# Core-Locobuffer.net
KiCad netlist of a schematic drawn in EAGLE
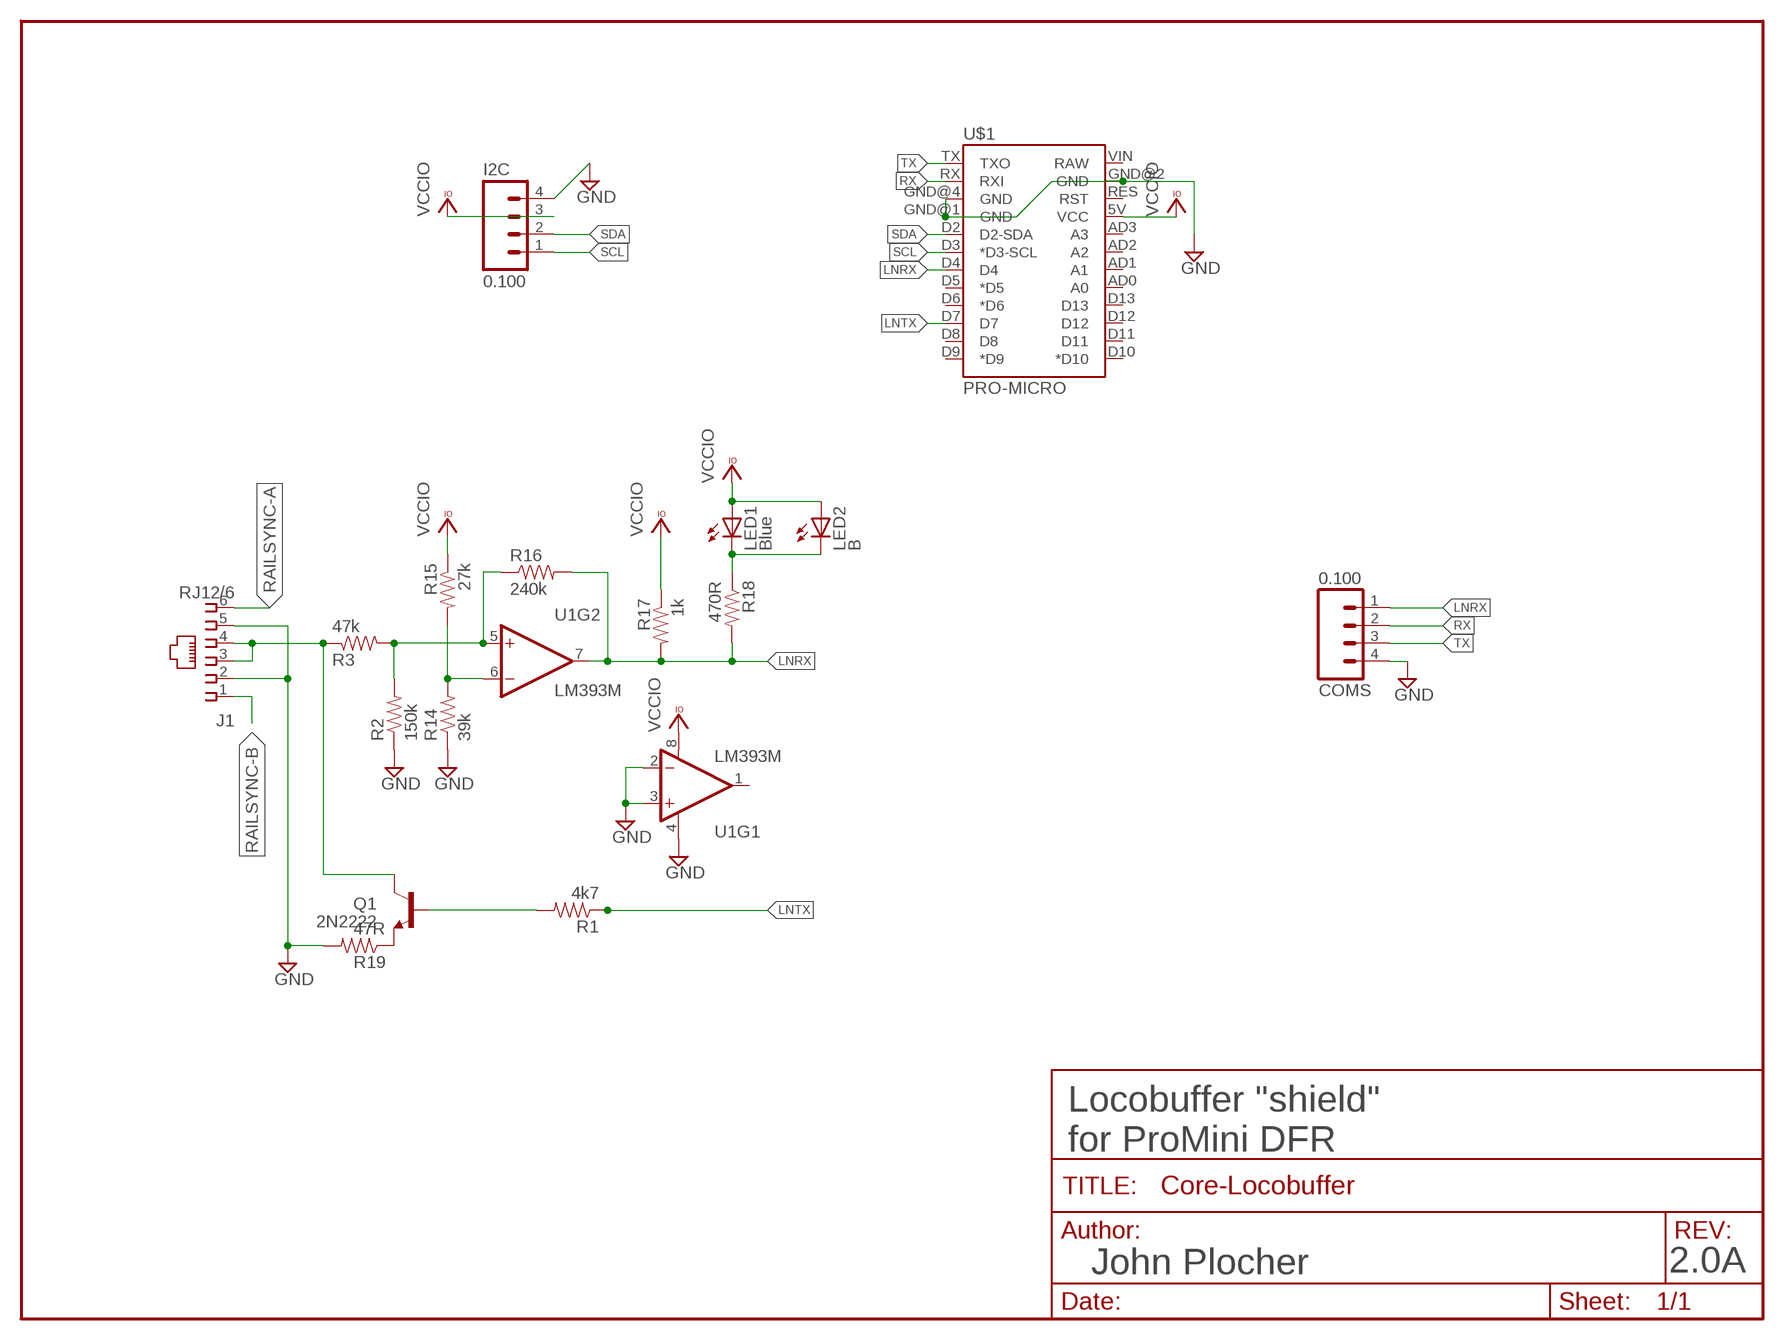
[diagram p0: schematic, sheet 1]

(export (version "E")
  (design (tool "Eeschema 10.0.6"))
  (components
    (comp (ref "COMS")
      (value "0.100")
      (footprint "eagle-import:1X04_LOCK")
      (libsource (lib "eagle-import") (part "CONNECTOR-M04LOCK"))
    )
    (comp (ref "I2C")
      (value "0.100")
      (footprint "eagle-import:1X04_LOCK")
      (libsource (lib "eagle-import") (part "CONNECTOR-M04LOCK"))
    )
    (comp (ref "J1")
      (value "RJ12/6")
      (footprint "eagle-import:RJ25-PANEL")
      (libsource (lib "eagle-import") (part "CONNECTOR-RJ25-6P6C"))
    )
    (comp (ref "LED1")
      (value "Blue")
      (footprint "eagle-import:0603-LED")
      (libsource (lib "eagle-import") (part "LED0603-LED"))
    )
    (comp (ref "LED2")
      (value "B")
      (footprint "eagle-import:LED5MM")
      (libsource (lib "eagle-import") (part "LEDLED5MM"))
    )
    (comp (ref "Q1")
      (value "2N2222")
      (footprint "eagle-import:SOT23")
      (libsource (lib "eagle-import") (part "NPN-SOT23"))
    )
    (comp (ref "R1")
      (value "4k7")
      (footprint "eagle-import:0603-RES")
      (libsource (lib "eagle-import") (part "R0603-RES"))
    )
    (comp (ref "R2")
      (value "150k")
      (footprint "eagle-import:0603-RES")
      (libsource (lib "eagle-import") (part "R0603-RES"))
    )
    (comp (ref "R3")
      (value "47k")
      (footprint "eagle-import:0603-RES")
      (libsource (lib "eagle-import") (part "R0603-RES"))
    )
    (comp (ref "R14")
      (value "39k")
      (footprint "eagle-import:0603-RES")
      (libsource (lib "eagle-import") (part "R0603-RES"))
    )
    (comp (ref "R15")
      (value "27k")
      (footprint "eagle-import:0603-RES")
      (libsource (lib "eagle-import") (part "R0603-RES"))
    )
    (comp (ref "R16")
      (value "240k")
      (footprint "eagle-import:0603-RES")
      (libsource (lib "eagle-import") (part "R0603-RES"))
    )
    (comp (ref "R17")
      (value "1k")
      (footprint "eagle-import:0603-RES")
      (libsource (lib "eagle-import") (part "R0603-RES"))
    )
    (comp (ref "R18")
      (value "470R")
      (footprint "eagle-import:0603-RES")
      (libsource (lib "eagle-import") (part "R0603-RES"))
    )
    (comp (ref "R19")
      (value "47R")
      (footprint "eagle-import:0603-RES")
      (libsource (lib "eagle-import") (part "R0603-RES"))
    )
    (comp (ref "U$1")
      (value "PRO-MICRO")
      (footprint "eagle-import:ARDUINO-PRO-MICRO-NOSILK")
      (libsource (lib "eagle-import") (part "ARDUINO-PRO-MICRO"))
    )
    (comp (ref "U1")
      (value "LM393M")
      (footprint "eagle-import:SO08")
      (libsource (lib "eagle-import") (part "LM393M"))
    )
  )
  (nets
    (net (code "1") (name "GND") (class "Default")
      (node (ref "COMS") (pin "4") (pinfunction "4_4") (pintype "passive"))
      (node (ref "I2C") (pin "4") (pinfunction "4_4") (pintype "passive"))
      (node (ref "J1") (pin "2") (pinfunction "2_2") (pintype "passive"))
      (node (ref "J1") (pin "5") (pinfunction "5_5") (pintype "passive"))
      (node (ref "R14") (pin "1") (pinfunction "1_1") (pintype "passive"))
      (node (ref "R19") (pin "2") (pinfunction "2_2") (pintype "passive"))
      (node (ref "R2") (pin "1") (pinfunction "1_1") (pintype "passive"))
      (node (ref "U$1") (pin "GND@1") (pinfunction "GND_GND@1") (pintype "bidirectional"))
      (node (ref "U$1") (pin "GND@2") (pinfunction "GND_GND@2") (pintype "bidirectional"))
      (node (ref "U$1") (pin "GND@4") (pinfunction "GND_GND@4") (pintype "bidirectional"))
      (node (ref "U1") (pin "2") (pinfunction "-IN_2") (pintype "input"))
      (node (ref "U1") (pin "3") (pinfunction "+IN_3") (pintype "input"))
      (node (ref "U1") (pin "4") (pinfunction "V-_4") (pintype "power_in"))
    )
    (net (code "2") (name "LNRX") (class "Default")
      (node (ref "COMS") (pin "1") (pinfunction "1_1") (pintype "passive"))
      (node (ref "R16") (pin "2") (pinfunction "2_2") (pintype "passive"))
      (node (ref "R17") (pin "2") (pinfunction "2_2") (pintype "passive"))
      (node (ref "R18") (pin "2") (pinfunction "2_2") (pintype "passive"))
      (node (ref "U$1") (pin "D4") (pinfunction "D4_D4") (pintype "bidirectional"))
      (node (ref "U1") (pin "7") (pinfunction "OUT_7") (pintype "output"))
    )
    (net (code "3") (name "LNTX") (class "Default")
      (node (ref "R1") (pin "1") (pinfunction "1_1") (pintype "passive"))
      (node (ref "U$1") (pin "D7") (pinfunction "D7_D7") (pintype "bidirectional"))
    )
    (net (code "4") (name "Net-(LED2-C)") (class "Default")
      (node (ref "LED1") (pin "C") (pinfunction "C_C") (pintype "passive"))
      (node (ref "LED2") (pin "K") (pinfunction "C_K") (pintype "passive"))
      (node (ref "R18") (pin "1") (pinfunction "1_1") (pintype "passive"))
    )
    (net (code "5") (name "Net-(Q1-B)") (class "Default")
      (node (ref "Q1") (pin "1") (pinfunction "B_1") (pintype "passive"))
      (node (ref "R1") (pin "2") (pinfunction "2_2") (pintype "passive"))
    )
    (net (code "6") (name "Net-(Q1-C)") (class "Default")
      (node (ref "J1") (pin "3") (pinfunction "3_3") (pintype "passive"))
      (node (ref "J1") (pin "4") (pinfunction "4_4") (pintype "passive"))
      (node (ref "Q1") (pin "3") (pinfunction "C_3") (pintype "passive"))
      (node (ref "R3") (pin "1") (pinfunction "1_1") (pintype "passive"))
    )
    (net (code "7") (name "Net-(Q1-E)") (class "Default")
      (node (ref "Q1") (pin "2") (pinfunction "E_2") (pintype "passive"))
      (node (ref "R19") (pin "1") (pinfunction "1_1") (pintype "passive"))
    )
    (net (code "8") (name "Net-(U1B-+IN)") (class "Default")
      (node (ref "R16") (pin "1") (pinfunction "1_1") (pintype "passive"))
      (node (ref "R2") (pin "2") (pinfunction "2_2") (pintype "passive"))
      (node (ref "R3") (pin "2") (pinfunction "2_2") (pintype "passive"))
      (node (ref "U1") (pin "5") (pinfunction "+IN_5") (pintype "input"))
    )
    (net (code "9") (name "Net-(U1B--IN)") (class "Default")
      (node (ref "R14") (pin "2") (pinfunction "2_2") (pintype "passive"))
      (node (ref "R15") (pin "2") (pinfunction "2_2") (pintype "passive"))
      (node (ref "U1") (pin "6") (pinfunction "-IN_6") (pintype "input"))
    )
    (net (code "10") (name "RAILSYNC-A") (class "Default")
      (node (ref "J1") (pin "6") (pinfunction "6_6") (pintype "passive"))
    )
    (net (code "11") (name "RAILSYNC-B") (class "Default")
      (node (ref "J1") (pin "1") (pinfunction "1_1") (pintype "passive"))
    )
    (net (code "12") (name "RX") (class "Default")
      (node (ref "COMS") (pin "2") (pinfunction "2_2") (pintype "passive"))
      (node (ref "U$1") (pin "RX") (pinfunction "RXI_RX") (pintype "bidirectional"))
    )
    (net (code "13") (name "SCL") (class "Default")
      (node (ref "I2C") (pin "1") (pinfunction "1_1") (pintype "passive"))
      (node (ref "U$1") (pin "D3") (pinfunction "*D3-SCL_D3") (pintype "bidirectional"))
    )
    (net (code "14") (name "SDA") (class "Default")
      (node (ref "I2C") (pin "2") (pinfunction "2_2") (pintype "passive"))
      (node (ref "U$1") (pin "D2") (pinfunction "D2-SDA_D2") (pintype "bidirectional"))
    )
    (net (code "15") (name "TX") (class "Default")
      (node (ref "COMS") (pin "3") (pinfunction "3_3") (pintype "passive"))
      (node (ref "U$1") (pin "TX") (pinfunction "TXO_TX") (pintype "bidirectional"))
    )
    (net (code "16") (name "VCCIO") (class "Default")
      (node (ref "I2C") (pin "3") (pinfunction "3_3") (pintype "passive"))
      (node (ref "LED1") (pin "A") (pinfunction "A_A") (pintype "passive"))
      (node (ref "LED2") (pin "A") (pinfunction "A_A") (pintype "passive"))
      (node (ref "R15") (pin "1") (pinfunction "1_1") (pintype "passive"))
      (node (ref "R17") (pin "1") (pinfunction "1_1") (pintype "passive"))
      (node (ref "U$1") (pin "5V") (pinfunction "VCC_5V") (pintype "bidirectional"))
      (node (ref "U1") (pin "8") (pinfunction "V+_8") (pintype "power_in"))
    )
    (net (code "17") (name "unconnected-(U$1-*D5-PadD5)") (class "Default")
      (node (ref "U$1") (pin "D5") (pinfunction "*D5_D5") (pintype "bidirectional"))
    )
    (net (code "18") (name "unconnected-(U$1-*D6-PadD6)") (class "Default")
      (node (ref "U$1") (pin "D6") (pinfunction "*D6_D6") (pintype "bidirectional"))
    )
    (net (code "19") (name "unconnected-(U$1-*D9-PadD9)") (class "Default")
      (node (ref "U$1") (pin "D9") (pinfunction "*D9_D9") (pintype "bidirectional"))
    )
    (net (code "20") (name "unconnected-(U$1-*D10-PadD10)") (class "Default")
      (node (ref "U$1") (pin "D10") (pinfunction "*D10_D10") (pintype "bidirectional"))
    )
    (net (code "21") (name "unconnected-(U$1-A0-PadAD0)") (class "Default")
      (node (ref "U$1") (pin "AD0") (pinfunction "A0_AD0") (pintype "bidirectional"))
    )
    (net (code "22") (name "unconnected-(U$1-A1-PadAD1)") (class "Default")
      (node (ref "U$1") (pin "AD1") (pinfunction "A1_AD1") (pintype "bidirectional"))
    )
    (net (code "23") (name "unconnected-(U$1-A2-PadAD2)") (class "Default")
      (node (ref "U$1") (pin "AD2") (pinfunction "A2_AD2") (pintype "bidirectional"))
    )
    (net (code "24") (name "unconnected-(U$1-A3-PadAD3)") (class "Default")
      (node (ref "U$1") (pin "AD3") (pinfunction "A3_AD3") (pintype "bidirectional"))
    )
    (net (code "25") (name "unconnected-(U$1-PadD8)") (class "Default")
      (node (ref "U$1") (pin "D8") (pinfunction "D8_D8") (pintype "bidirectional"))
    )
    (net (code "26") (name "unconnected-(U$1-PadD11)") (class "Default")
      (node (ref "U$1") (pin "D11") (pinfunction "D11_D11") (pintype "bidirectional"))
    )
    (net (code "27") (name "unconnected-(U$1-PadD12)") (class "Default")
      (node (ref "U$1") (pin "D12") (pinfunction "D12_D12") (pintype "bidirectional"))
    )
    (net (code "28") (name "unconnected-(U$1-PadD13)") (class "Default")
      (node (ref "U$1") (pin "D13") (pinfunction "D13_D13") (pintype "bidirectional"))
    )
    (net (code "29") (name "unconnected-(U$1-RAW-PadVIN)") (class "Default")
      (node (ref "U$1") (pin "VIN") (pinfunction "RAW_VIN") (pintype "bidirectional"))
    )
    (net (code "30") (name "unconnected-(U$1-RST-PadRES)") (class "Default")
      (node (ref "U$1") (pin "RES") (pinfunction "RST_RES") (pintype "bidirectional"))
    )
    (net (code "31") (name "unconnected-(U1A-OUT-Pad1)") (class "Default")
      (node (ref "U1") (pin "1") (pinfunction "OUT_1") (pintype "output"))
    )
  )
)
